# Electrode_Monitor_Channel.net
KiCad netlist of a schematic drawn in Altium Designer
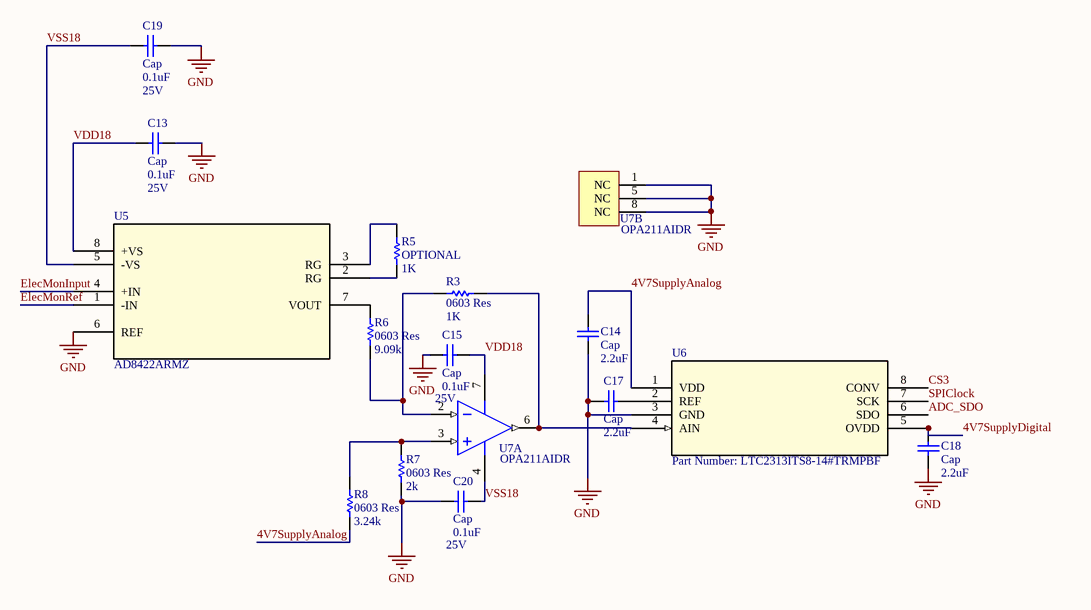
[diagram p0: Electrode Monitor Channel.SchDoc]

(export (version "E")
  (design (tool "Eeschema 10.0.6"))
  (components
    (comp (ref "C13")
      (value "Cap")
      (footprint "1608[0603]")
      (description "Capacitor")
      (fields
        (field (name "ALTIUM_VALUE") "0.1uF")
        (field (name "RATED VOLTAGE") "25V")
        (field (name "PUBLISHER") "Altium Limited")
      )
      (libsource (lib "Miscellaneous Devices") (part "Cap"))
    )
    (comp (ref "C14")
      (value "Cap")
      (footprint "1608[0603]")
      (description "Capacitor")
      (fields (field (name "ALTIUM_VALUE") "2.2uF") (field (name "PUBLISHER") "Altium Limited"))
      (libsource (lib "Miscellaneous Devices") (part "Cap"))
    )
    (comp (ref "C15")
      (value "Cap")
      (footprint "1608[0603]")
      (description "Capacitor")
      (fields
        (field (name "ALTIUM_VALUE") "0.1uF")
        (field (name "RATED VOLTAGE") "25V")
        (field (name "PUBLISHER") "Altium Limited")
      )
      (libsource (lib "Miscellaneous Devices") (part "Cap"))
    )
    (comp (ref "C17")
      (value "Cap")
      (footprint "1608[0603]")
      (description "Capacitor")
      (fields (field (name "ALTIUM_VALUE") "2.2uF") (field (name "PUBLISHER") "Altium Limited"))
      (libsource (lib "Miscellaneous Devices") (part "Cap"))
    )
    (comp (ref "C18")
      (value "Cap")
      (footprint "1608[0603]")
      (description "Capacitor")
      (fields (field (name "ALTIUM_VALUE") "2.2uF") (field (name "PUBLISHER") "Altium Limited"))
      (libsource (lib "Miscellaneous Devices") (part "Cap"))
    )
    (comp (ref "C19")
      (value "Cap")
      (footprint "1608[0603]")
      (description "Capacitor")
      (fields
        (field (name "ALTIUM_VALUE") "0.1uF")
        (field (name "RATED VOLTAGE") "25V")
        (field (name "PUBLISHER") "Altium Limited")
      )
      (libsource (lib "Miscellaneous Devices") (part "Cap"))
    )
    (comp (ref "C20")
      (value "Cap")
      (footprint "1608[0603]")
      (description "Capacitor")
      (fields
        (field (name "ALTIUM_VALUE") "0.1uF")
        (field (name "RATED VOLTAGE") "25V")
        (field (name "PUBLISHER") "Altium Limited")
      )
      (libsource (lib "Miscellaneous Devices") (part "Cap"))
    )
    (comp (ref "R3")
      (value "0603 Res")
      (footprint "J1-0603")
      (description "Resistor, gain-setting (OPTIONAL), 0603")
      (fields (field (name "ALTIUM_VALUE") "1K") (field (name "PUBLISHER") "Altium Limited"))
      (libsource (lib "Miscellaneous Devices") (part "Res1"))
    )
    (comp (ref "R5")
      (value "OPTIONAL")
      (footprint "J1-0603")
      (description "Resistor, gain-setting (OPTIONAL), 0603")
      (fields (field (name "ALTIUM_VALUE") "1K") (field (name "PUBLISHER") "Altium Limited"))
      (libsource (lib "Miscellaneous Devices") (part "Res1"))
    )
    (comp (ref "R6")
      (value "0603 Res")
      (footprint "J1-0603")
      (description "Resistor, gain-setting (OPTIONAL), 0603")
      (fields (field (name "ALTIUM_VALUE") "9.09k") (field (name "PUBLISHER") "Altium Limited"))
      (libsource (lib "Miscellaneous Devices") (part "Res1"))
    )
    (comp (ref "R7")
      (value "0603 Res")
      (footprint "J1-0603")
      (description "Resistor, gain-setting (OPTIONAL), 0603")
      (fields (field (name "ALTIUM_VALUE") "2k") (field (name "PUBLISHER") "Altium Limited"))
      (libsource (lib "Miscellaneous Devices") (part "Res1"))
    )
    (comp (ref "R8")
      (value "0603 Res")
      (footprint "J1-0603")
      (description "Resistor, gain-setting (OPTIONAL), 0603")
      (fields (field (name "ALTIUM_VALUE") "3.24k") (field (name "PUBLISHER") "Altium Limited"))
      (libsource (lib "Miscellaneous Devices") (part "Res1"))
    )
    (comp (ref "U5")
      (value "AD8422ARMZ")
      (footprint "MSOP-8")
      (description "IC OPAMP INSTR 2.2MHZ RRO 8MSOP")
      (fields (field (name "COPYRIGHT") "Copyright (C) 2018 Accelerated Designs. All rights reserved"))
      (libsource (lib "ar5113_Altium_Library") (part "AD8422ARMZ"))
    )
    (comp (ref "U6")
      (value "Part Number: LTC2313ITS8-14#TRMPBF")
      (footprint "TSOT-23_TS8")
      (description "14-bit 2.5MSPS Single-Ended ADC, 3-5V single supply on TSOT-8")
      (fields
        (field (name "MANUFACTURER_PART_NUMBER") "LTC2313ITS8-14#TRMPBF")
        (field (name "COPYRIGHT") "Copyright (C) 2018 Accelerated Designs. All rights reserved")
      )
      (libsource (lib "ar5113_Altium_Library") (part "LTC2313ITS8-14#T"))
    )
    (comp (ref "U7")
      (value "OPA211AIDR")
      (footprint "TI-D8_L")
      (fields (field (name "MANUFACTURER") "Texas Instruments"))
      (libsource (lib "Altium Content Vault") (part "TI-OPA-8_1"))
    )
  )
  (nets
    (net (code "1") (name "/4V7SupplyAnalog") (class "Default")
      (node (ref "C14") (pin "2") (pinfunction "2_2") (pintype "passive"))
      (node (ref "R8") (pin "2") (pinfunction "2_2") (pintype "passive"))
      (node (ref "U6") (pin "1") (pinfunction "VDD_1") (pintype "power_in"))
    )
    (net (code "2") (name "/4V7SupplyDigital") (class "Default")
      (node (ref "C18") (pin "2") (pinfunction "2_2") (pintype "passive"))
      (node (ref "U6") (pin "5") (pinfunction "OVDD_5") (pintype "power_in"))
    )
    (net (code "3") (name "/ADC_SDO") (class "Default")
      (node (ref "U6") (pin "6") (pinfunction "SDO_6") (pintype "passive"))
    )
    (net (code "4") (name "/CS3") (class "Default")
      (node (ref "U6") (pin "8") (pinfunction "CONV_8") (pintype "passive"))
    )
    (net (code "5") (name "/ElecMonInput") (class "Default")
      (node (ref "U5") (pin "4") (pinfunction "+IN_4") (pintype "passive"))
    )
    (net (code "6") (name "/ElecMonRef") (class "Default")
      (node (ref "U5") (pin "1") (pinfunction "-IN_1") (pintype "passive"))
    )
    (net (code "7") (name "/SPIClock") (class "Default")
      (node (ref "U6") (pin "7") (pinfunction "SCK_7") (pintype "passive"))
    )
    (net (code "8") (name "/VDD18") (class "Default")
      (node (ref "C13") (pin "2") (pinfunction "2_2") (pintype "passive"))
      (node (ref "C15") (pin "2") (pinfunction "2_2") (pintype "passive"))
      (node (ref "U5") (pin "8") (pinfunction "+VS_8") (pintype "passive"))
      (node (ref "U7") (pin "7") (pinfunction "V+_7") (pintype "power_in"))
    )
    (net (code "9") (name "/VSS18") (class "Default")
      (node (ref "C19") (pin "2") (pinfunction "2_2") (pintype "passive"))
      (node (ref "C20") (pin "2") (pinfunction "2_2") (pintype "passive"))
      (node (ref "U5") (pin "5") (pinfunction "-VS_5") (pintype "passive"))
      (node (ref "U7") (pin "4") (pinfunction "V-_4") (pintype "power_in"))
    )
    (net (code "10") (name "GND") (class "Default")
      (node (ref "C13") (pin "1") (pinfunction "1_1") (pintype "passive"))
      (node (ref "C14") (pin "1") (pinfunction "1_1") (pintype "passive"))
      (node (ref "C15") (pin "1") (pinfunction "1_1") (pintype "passive"))
      (node (ref "C17") (pin "1") (pinfunction "1_1") (pintype "passive"))
      (node (ref "C18") (pin "1") (pinfunction "1_1") (pintype "passive"))
      (node (ref "C19") (pin "1") (pinfunction "1_1") (pintype "passive"))
      (node (ref "C20") (pin "1") (pinfunction "1_1") (pintype "passive"))
      (node (ref "R7") (pin "2") (pinfunction "2_2") (pintype "passive"))
      (node (ref "U5") (pin "6") (pinfunction "REF_6") (pintype "passive"))
      (node (ref "U6") (pin "3") (pinfunction "GND_3") (pintype "power_in"))
      (node (ref "U7") (pin "1") (pinfunction "NC_1") (pintype "passive"))
      (node (ref "U7") (pin "5") (pinfunction "NC_5") (pintype "passive"))
      (node (ref "U7") (pin "8") (pinfunction "NC_8") (pintype "passive"))
    )
    (net (code "11") (name "Net-(R5-Pad1)") (class "Default")
      (node (ref "R5") (pin "1") (pinfunction "1_1") (pintype "passive"))
      (node (ref "U5") (pin "2") (pinfunction "RG_2") (pintype "passive"))
    )
    (net (code "12") (name "Net-(R5-Pad2)") (class "Default")
      (node (ref "R5") (pin "2") (pinfunction "2_2") (pintype "passive"))
      (node (ref "U5") (pin "3") (pinfunction "RG_3") (pintype "passive"))
    )
    (net (code "13") (name "Net-(U5-VOUT)") (class "Default")
      (node (ref "R6") (pin "2") (pinfunction "2_2") (pintype "passive"))
      (node (ref "U5") (pin "7") (pinfunction "VOUT_7") (pintype "passive"))
    )
    (net (code "14") (name "Net-(U6-AIN)") (class "Default")
      (node (ref "R3") (pin "1") (pinfunction "1_1") (pintype "passive"))
      (node (ref "U6") (pin "4") (pinfunction "AIN_4") (pintype "input"))
      (node (ref "U7") (pin "6") (pinfunction "OUT_6") (pintype "output"))
    )
    (net (code "15") (name "Net-(U6-REF)") (class "Default")
      (node (ref "C17") (pin "2") (pinfunction "2_2") (pintype "passive"))
      (node (ref "U6") (pin "2") (pinfunction "REF_2") (pintype "passive"))
    )
    (net (code "16") (name "Net-(U7A-IN+)") (class "Default")
      (node (ref "R7") (pin "1") (pinfunction "1_1") (pintype "passive"))
      (node (ref "R8") (pin "1") (pinfunction "1_1") (pintype "passive"))
      (node (ref "U7") (pin "3") (pinfunction "IN+_3") (pintype "input"))
    )
    (net (code "17") (name "Net-(U7A-IN-)") (class "Default")
      (node (ref "R3") (pin "2") (pinfunction "2_2") (pintype "passive"))
      (node (ref "R6") (pin "1") (pinfunction "1_1") (pintype "passive"))
      (node (ref "U7") (pin "2") (pinfunction "IN-_2") (pintype "input"))
    )
  )
)
